# MeterMaidV2.net
KiCad netlist of a schematic drawn in EAGLE
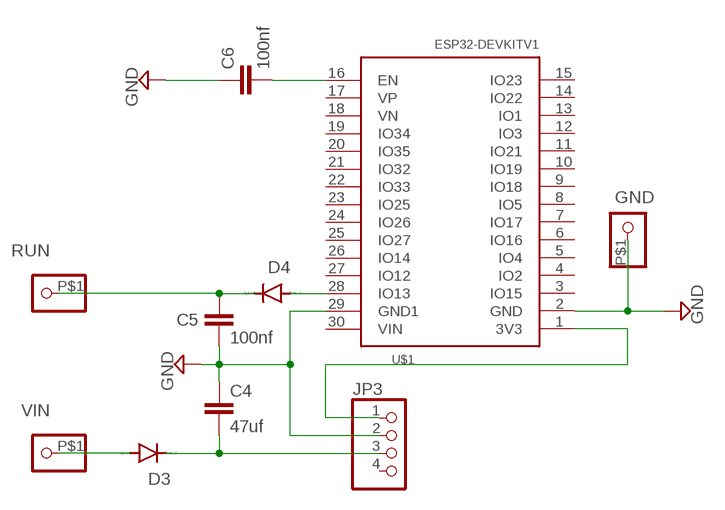
[diagram p0: schematic, sheet 1]

(export (version "E")
  (design (tool "Eeschema 10.0.6"))
  (components
    (comp (ref "C4")
      (value "47uf")
      (footprint "eagle-import:C025-050X050")
      (libsource (lib "eagle-import") (part "C-EU025-050X050"))
    )
    (comp (ref "C5")
      (value "100nf")
      (footprint "eagle-import:C025-050X050")
      (libsource (lib "eagle-import") (part "C-EU025-050X050"))
    )
    (comp (ref "C6")
      (value "100nf")
      (footprint "eagle-import:C025-050X050")
      (libsource (lib "eagle-import") (part "C-EU025-050X050"))
    )
    (comp (ref "D3")
      (value "1N4004")
      (footprint "eagle-import:DO41-10")
      (libsource (lib "eagle-import") (part "1N4004"))
    )
    (comp (ref "D4")
      (value "1N4004")
      (footprint "eagle-import:DO41-10")
      (libsource (lib "eagle-import") (part "1N4004"))
    )
    (comp (ref "GND")
      (value "PINHD-1X11X02")
      (footprint "eagle-import:1X01LP")
      (libsource (lib "eagle-import") (part "PINHD-1X11X02"))
    )
    (comp (ref "JP3")
      (value "PINHD-1X4")
      (footprint "eagle-import:1X04")
      (libsource (lib "eagle-import") (part "PINHD-1X4"))
    )
    (comp (ref "RUN")
      (value "PINHD-1X11X02")
      (footprint "eagle-import:1X01LP")
      (libsource (lib "eagle-import") (part "PINHD-1X11X02"))
    )
    (comp (ref "U$1")
      (value "ESP32DEVKITV1ESP32-DEVKITV2")
      (footprint "eagle-import:ESP32-DEVKITV2")
      (libsource (lib "eagle-import") (part "ESP32DEVKITV1ESP32-DEVKITV2"))
    )
    (comp (ref "VIN")
      (value "PINHD-1X11X02")
      (footprint "eagle-import:1X01LP")
      (libsource (lib "eagle-import") (part "PINHD-1X11X02"))
    )
  )
  (nets
    (net (code "1") (name "GND") (class "Default")
      (node (ref "C4") (pin "1") (pinfunction "1_1") (pintype "passive"))
      (node (ref "C5") (pin "2") (pinfunction "2_2") (pintype "passive"))
      (node (ref "C6") (pin "1") (pinfunction "1_1") (pintype "passive"))
      (node (ref "GND") (pin "P$1") (pinfunction "1_P$1") (pintype "passive"))
      (node (ref "JP3") (pin "2") (pinfunction "2_2") (pintype "passive"))
      (node (ref "U$1") (pin "2") (pinfunction "GND_2") (pintype "bidirectional"))
      (node (ref "U$1") (pin "29") (pinfunction "GND1_29") (pintype "bidirectional"))
    )
    (net (code "2") (name "Net-(C4-Pad2)") (class "Default")
      (node (ref "C4") (pin "2") (pinfunction "2_2") (pintype "passive"))
      (node (ref "D3") (pin "C") (pinfunction "C_C") (pintype "passive"))
      (node (ref "JP3") (pin "3") (pinfunction "3_3") (pintype "passive"))
    )
    (net (code "3") (name "Net-(RUN-1)") (class "Default")
      (node (ref "C5") (pin "1") (pinfunction "1_1") (pintype "passive"))
      (node (ref "D4") (pin "C") (pinfunction "C_C") (pintype "passive"))
      (node (ref "RUN") (pin "P$1") (pinfunction "1_P$1") (pintype "passive"))
    )
    (net (code "4") (name "Net-(U$1-3V3)") (class "Default")
      (node (ref "JP3") (pin "1") (pinfunction "1_1") (pintype "passive"))
      (node (ref "U$1") (pin "1") (pinfunction "3V3_1") (pintype "bidirectional"))
    )
    (net (code "5") (name "Net-(U$1-EN)") (class "Default")
      (node (ref "C6") (pin "2") (pinfunction "2_2") (pintype "passive"))
      (node (ref "U$1") (pin "16") (pinfunction "EN_16") (pintype "bidirectional"))
    )
    (net (code "6") (name "Net-(U$1-IO13)") (class "Default")
      (node (ref "D4") (pin "A") (pinfunction "A_A") (pintype "passive"))
      (node (ref "U$1") (pin "28") (pinfunction "IO13_28") (pintype "bidirectional"))
    )
    (net (code "7") (name "Net-(VIN-1)") (class "Default")
      (node (ref "D3") (pin "A") (pinfunction "A_A") (pintype "passive"))
      (node (ref "VIN") (pin "P$1") (pinfunction "1_P$1") (pintype "passive"))
    )
    (net (code "8") (name "unconnected-(JP3-Pad4)") (class "Default")
      (node (ref "JP3") (pin "4") (pinfunction "4_4") (pintype "passive"))
    )
    (net (code "9") (name "unconnected-(U$1-IO1-Pad13)") (class "Default")
      (node (ref "U$1") (pin "13") (pinfunction "IO1_13") (pintype "bidirectional"))
    )
    (net (code "10") (name "unconnected-(U$1-IO2-Pad4)") (class "Default")
      (node (ref "U$1") (pin "4") (pinfunction "IO2_4") (pintype "bidirectional"))
    )
    (net (code "11") (name "unconnected-(U$1-IO3-Pad12)") (class "Default")
      (node (ref "U$1") (pin "12") (pinfunction "IO3_12") (pintype "bidirectional"))
    )
    (net (code "12") (name "unconnected-(U$1-IO4-Pad5)") (class "Default")
      (node (ref "U$1") (pin "5") (pinfunction "IO4_5") (pintype "bidirectional"))
    )
    (net (code "13") (name "unconnected-(U$1-IO5-Pad8)") (class "Default")
      (node (ref "U$1") (pin "8") (pinfunction "IO5_8") (pintype "bidirectional"))
    )
    (net (code "14") (name "unconnected-(U$1-IO12-Pad27)") (class "Default")
      (node (ref "U$1") (pin "27") (pinfunction "IO12_27") (pintype "bidirectional"))
    )
    (net (code "15") (name "unconnected-(U$1-IO14-Pad26)") (class "Default")
      (node (ref "U$1") (pin "26") (pinfunction "IO14_26") (pintype "bidirectional"))
    )
    (net (code "16") (name "unconnected-(U$1-IO15-Pad3)") (class "Default")
      (node (ref "U$1") (pin "3") (pinfunction "IO15_3") (pintype "bidirectional"))
    )
    (net (code "17") (name "unconnected-(U$1-IO16-Pad6)") (class "Default")
      (node (ref "U$1") (pin "6") (pinfunction "IO16_6") (pintype "bidirectional"))
    )
    (net (code "18") (name "unconnected-(U$1-IO17-Pad7)") (class "Default")
      (node (ref "U$1") (pin "7") (pinfunction "IO17_7") (pintype "bidirectional"))
    )
    (net (code "19") (name "unconnected-(U$1-IO18-Pad9)") (class "Default")
      (node (ref "U$1") (pin "9") (pinfunction "IO18_9") (pintype "bidirectional"))
    )
    (net (code "20") (name "unconnected-(U$1-IO19-Pad10)") (class "Default")
      (node (ref "U$1") (pin "10") (pinfunction "IO19_10") (pintype "bidirectional"))
    )
    (net (code "21") (name "unconnected-(U$1-IO21-Pad11)") (class "Default")
      (node (ref "U$1") (pin "11") (pinfunction "IO21_11") (pintype "bidirectional"))
    )
    (net (code "22") (name "unconnected-(U$1-IO22-Pad14)") (class "Default")
      (node (ref "U$1") (pin "14") (pinfunction "IO22_14") (pintype "bidirectional"))
    )
    (net (code "23") (name "unconnected-(U$1-IO23-Pad15)") (class "Default")
      (node (ref "U$1") (pin "15") (pinfunction "IO23_15") (pintype "bidirectional"))
    )
    (net (code "24") (name "unconnected-(U$1-IO25-Pad23)") (class "Default")
      (node (ref "U$1") (pin "23") (pinfunction "IO25_23") (pintype "bidirectional"))
    )
    (net (code "25") (name "unconnected-(U$1-IO26-Pad24)") (class "Default")
      (node (ref "U$1") (pin "24") (pinfunction "IO26_24") (pintype "bidirectional"))
    )
    (net (code "26") (name "unconnected-(U$1-IO27-Pad25)") (class "Default")
      (node (ref "U$1") (pin "25") (pinfunction "IO27_25") (pintype "bidirectional"))
    )
    (net (code "27") (name "unconnected-(U$1-IO32-Pad21)") (class "Default")
      (node (ref "U$1") (pin "21") (pinfunction "IO32_21") (pintype "bidirectional"))
    )
    (net (code "28") (name "unconnected-(U$1-IO33-Pad22)") (class "Default")
      (node (ref "U$1") (pin "22") (pinfunction "IO33_22") (pintype "bidirectional"))
    )
    (net (code "29") (name "unconnected-(U$1-IO34-Pad19)") (class "Default")
      (node (ref "U$1") (pin "19") (pinfunction "IO34_19") (pintype "bidirectional"))
    )
    (net (code "30") (name "unconnected-(U$1-IO35-Pad20)") (class "Default")
      (node (ref "U$1") (pin "20") (pinfunction "IO35_20") (pintype "bidirectional"))
    )
    (net (code "31") (name "unconnected-(U$1-VIN-Pad30)") (class "Default")
      (node (ref "U$1") (pin "30") (pinfunction "VIN_30") (pintype "bidirectional"))
    )
    (net (code "32") (name "unconnected-(U$1-VN-Pad18)") (class "Default")
      (node (ref "U$1") (pin "18") (pinfunction "VN_18") (pintype "bidirectional"))
    )
    (net (code "33") (name "unconnected-(U$1-VP-Pad17)") (class "Default")
      (node (ref "U$1") (pin "17") (pinfunction "VP_17") (pintype "bidirectional"))
    )
  )
)
